# placa_1.net
KiCad netlist of a schematic drawn in EAGLE
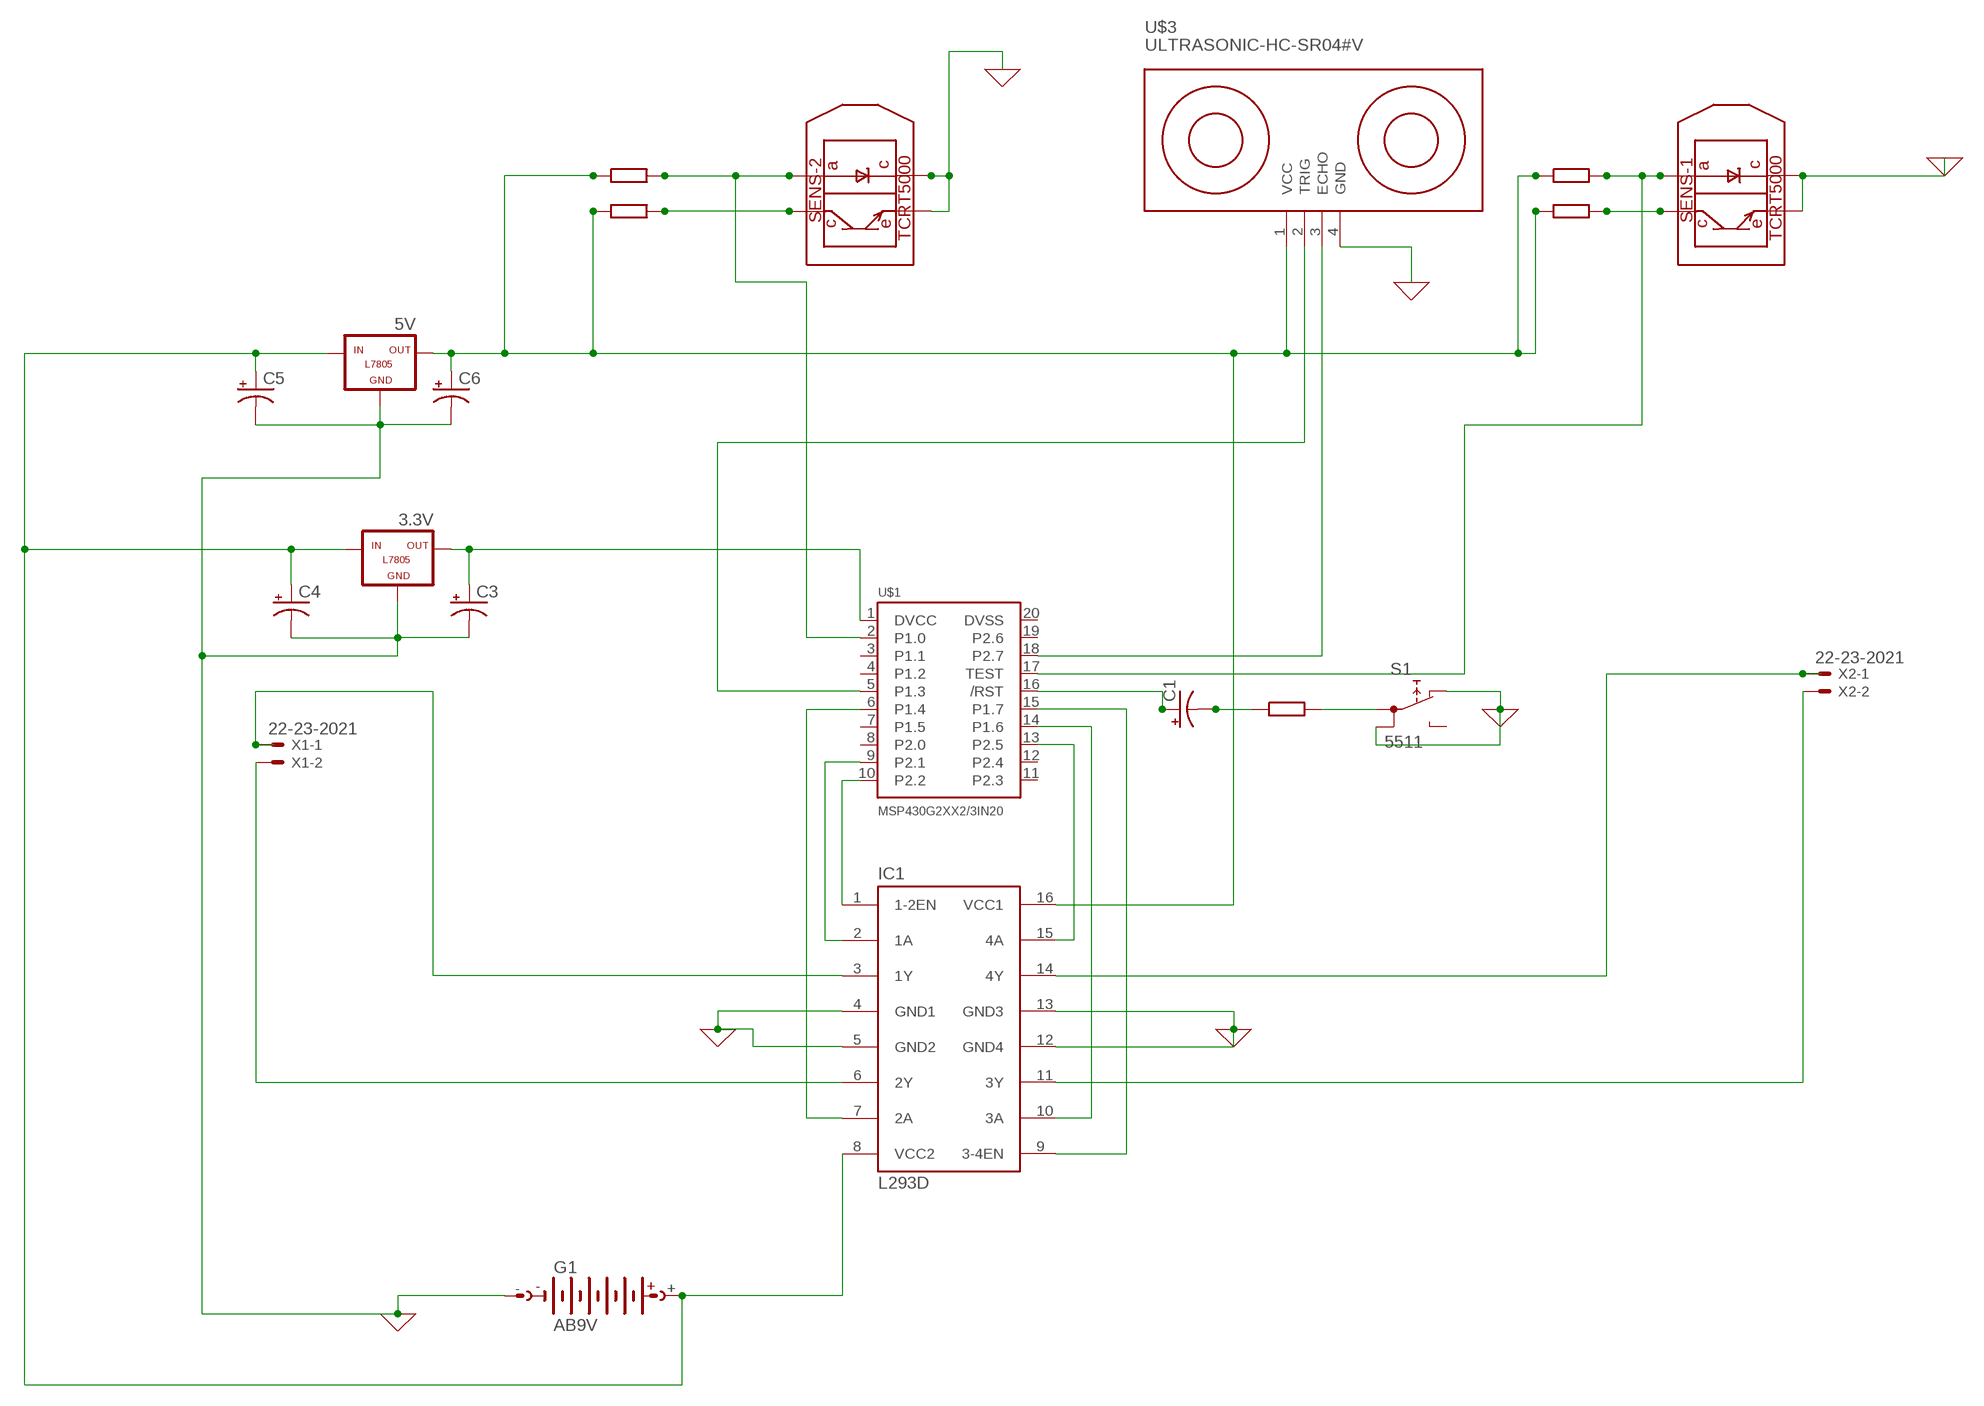
[diagram p0: schematic, sheet 1]

(export (version "E")
  (design (tool "Eeschema 10.0.6"))
  (components
    (comp (ref "3.3V")
      (value "-L7805")
      (footprint "eagle-import:L7805")
      (libsource (lib "eagle-import") (part "-L7805"))
    )
    (comp (ref "5V")
      (value "-L7805")
      (footprint "eagle-import:L7805")
      (libsource (lib "eagle-import") (part "-L7805"))
    )
    (comp (ref "C1")
      (value "CPOL-US085CS-1R")
      (footprint "eagle-import:085CS_1R")
      (libsource (lib "eagle-import") (part "CPOL-US085CS-1R"))
    )
    (comp (ref "C3")
      (value "CPOL-US085CS-1R")
      (footprint "eagle-import:085CS_1R")
      (libsource (lib "eagle-import") (part "CPOL-US085CS-1R"))
    )
    (comp (ref "C4")
      (value "CPOL-US085CS-1R")
      (footprint "eagle-import:085CS_1R")
      (libsource (lib "eagle-import") (part "CPOL-US085CS-1R"))
    )
    (comp (ref "C5")
      (value "CPOL-US085CS-1R")
      (footprint "eagle-import:085CS_1R")
      (libsource (lib "eagle-import") (part "CPOL-US085CS-1R"))
    )
    (comp (ref "C6")
      (value "CPOL-US085CS-1R")
      (footprint "eagle-import:085CS_1R")
      (libsource (lib "eagle-import") (part "CPOL-US085CS-1R"))
    )
    (comp (ref "G1")
      (value "AB9V")
      (footprint "eagle-import:AB9V")
      (libsource (lib "eagle-import") (part "AB9V"))
    )
    (comp (ref "IC1")
      (value "L293D")
      (footprint "eagle-import:DIL16")
      (libsource (lib "eagle-import") (part "L293D"))
    )
    (comp (ref "S1")
      (value "5511")
      (footprint "eagle-import:5511")
      (libsource (lib "eagle-import") (part "55?11"))
    )
    (comp (ref "SENS-1")
      (value "TCRT5000")
      (footprint "eagle-import:5000")
      (libsource (lib "eagle-import") (part "TCRT5000"))
    )
    (comp (ref "SENS-2")
      (value "TCRT5000")
      (footprint "eagle-import:5000")
      (libsource (lib "eagle-import") (part "TCRT5000"))
    )
    (comp (ref "U$1")
      (value "MSP430G2XX2/3IN20")
      (footprint "eagle-import:DIL20")
      (libsource (lib "eagle-import") (part "MSP430G2XX2/3IN20"))
    )
    (comp (ref "U$3")
      (value "ULTRASONIC-HC-SR04#V")
      (footprint "eagle-import:ULTRASONIC-HC-SR04#V")
      (libsource (lib "eagle-import") (part "ULTRASONIC-HC-SR04#V"))
    )
    (comp (ref "X1")
      (value "22-23-2021")
      (footprint "eagle-import:22-23-2021")
      (fields (field (name "MF") "MOLEX"))
      (libsource (lib "eagle-import") (part "22-23-2021"))
    )
    (comp (ref "X2")
      (value "22-23-2021")
      (footprint "eagle-import:22-23-2021")
      (fields (field (name "MF") "MOLEX"))
      (libsource (lib "eagle-import") (part "22-23-2021"))
    )
  )
  (nets
    (net (code "1") (name "/DVSS") (class "Default")
      (node (ref "U$1") (pin "20") (pinfunction "DVSS_20") (pintype "power_in"))
    )
    (net (code "2") (name "GND") (class "Default")
      (node (ref "3.3V") (pin "GND") (pinfunction "GND_GND") (pintype "input"))
      (node (ref "5V") (pin "GND") (pinfunction "GND_GND") (pintype "input"))
      (node (ref "C3") (pin "-") (pinfunction "-_-") (pintype "passive"))
      (node (ref "C4") (pin "-") (pinfunction "-_-") (pintype "passive"))
      (node (ref "C5") (pin "-") (pinfunction "-_-") (pintype "passive"))
      (node (ref "C6") (pin "-") (pinfunction "-_-") (pintype "passive"))
      (node (ref "G1") (pin "-") (pinfunction "-_-") (pintype "passive"))
      (node (ref "IC1") (pin "12") (pinfunction "GND4_12") (pintype "power_in"))
      (node (ref "IC1") (pin "13") (pinfunction "GND3_13") (pintype "power_in"))
      (node (ref "IC1") (pin "4") (pinfunction "GND1_4") (pintype "power_in"))
      (node (ref "IC1") (pin "5") (pinfunction "GND2_5") (pintype "power_in"))
      (node (ref "S1") (pin "1B") (pinfunction "1B_1B") (pintype "passive"))
      (node (ref "S1") (pin "NC") (pinfunction "NC_NC") (pintype "passive"))
      (node (ref "SENS-1") (pin "P$2") (pinfunction "P$2_P$2") (pintype "passive"))
      (node (ref "SENS-1") (pin "P$4") (pinfunction "P$4_P$4") (pintype "passive"))
      (node (ref "SENS-2") (pin "P$2") (pinfunction "P$2_P$2") (pintype "passive"))
      (node (ref "SENS-2") (pin "P$4") (pinfunction "P$4_P$4") (pintype "passive"))
      (node (ref "U$3") (pin "4") (pinfunction "GND_4") (pintype "power_in"))
    )
    (net (code "3") (name "Net-(IC1-1-2EN)") (class "Default")
      (node (ref "IC1") (pin "1") (pinfunction "1-2EN_1") (pintype "input"))
      (node (ref "U$1") (pin "10") (pinfunction "P2.2_10") (pintype "bidirectional"))
    )
    (net (code "4") (name "Net-(IC1-1A)") (class "Default")
      (node (ref "IC1") (pin "2") (pinfunction "1A_2") (pintype "input"))
      (node (ref "U$1") (pin "9") (pinfunction "P2.1_9") (pintype "bidirectional"))
    )
    (net (code "5") (name "Net-(IC1-1Y)") (class "Default")
      (node (ref "IC1") (pin "3") (pinfunction "1Y_3") (pintype "output"))
      (node (ref "X1") (pin "1") (pinfunction "S_1") (pintype "passive"))
    )
    (net (code "6") (name "Net-(IC1-2A)") (class "Default")
      (node (ref "IC1") (pin "7") (pinfunction "2A_7") (pintype "input"))
      (node (ref "U$1") (pin "6") (pinfunction "P1.4_6") (pintype "bidirectional"))
    )
    (net (code "7") (name "Net-(IC1-2Y)") (class "Default")
      (node (ref "IC1") (pin "6") (pinfunction "2Y_6") (pintype "output"))
      (node (ref "X1") (pin "2") (pinfunction "S_2") (pintype "passive"))
    )
    (net (code "8") (name "Net-(IC1-3-4EN)") (class "Default")
      (node (ref "IC1") (pin "9") (pinfunction "3-4EN_9") (pintype "input"))
      (node (ref "U$1") (pin "15") (pinfunction "P1.7_15") (pintype "bidirectional"))
    )
    (net (code "9") (name "Net-(IC1-3A)") (class "Default")
      (node (ref "IC1") (pin "10") (pinfunction "3A_10") (pintype "input"))
      (node (ref "U$1") (pin "14") (pinfunction "P1.6_14") (pintype "bidirectional"))
    )
    (net (code "10") (name "Net-(IC1-3Y)") (class "Default")
      (node (ref "IC1") (pin "11") (pinfunction "3Y_11") (pintype "output"))
      (node (ref "X2") (pin "2") (pinfunction "S_2") (pintype "passive"))
    )
    (net (code "11") (name "Net-(IC1-4A)") (class "Default")
      (node (ref "IC1") (pin "15") (pinfunction "4A_15") (pintype "input"))
      (node (ref "U$1") (pin "13") (pinfunction "P2.5_13") (pintype "bidirectional"))
    )
    (net (code "12") (name "Net-(IC1-4Y)") (class "Default")
      (node (ref "IC1") (pin "14") (pinfunction "4Y_14") (pintype "output"))
      (node (ref "X2") (pin "1") (pinfunction "S_1") (pintype "passive"))
    )
    (net (code "13") (name "Net-(IC1-VCC1)") (class "Default")
      (node (ref "5V") (pin "OUT") (pinfunction "OUT_OUT") (pintype "passive"))
      (node (ref "C6") (pin "+") (pinfunction "+_+") (pintype "passive"))
      (node (ref "IC1") (pin "16") (pinfunction "VCC1_16") (pintype "power_in"))
      (node (ref "U$3") (pin "1") (pinfunction "VCC_1") (pintype "power_in"))
    )
    (net (code "14") (name "Net-(IC1-VCC2)") (class "Default")
      (node (ref "3.3V") (pin "IN") (pinfunction "IN_IN") (pintype "input"))
      (node (ref "5V") (pin "IN") (pinfunction "IN_IN") (pintype "input"))
      (node (ref "C4") (pin "+") (pinfunction "+_+") (pintype "passive"))
      (node (ref "C5") (pin "+") (pinfunction "+_+") (pintype "passive"))
      (node (ref "G1") (pin "+") (pinfunction "+_+") (pintype "passive"))
      (node (ref "IC1") (pin "8") (pinfunction "VCC2_8") (pintype "power_in"))
    )
    (net (code "15") (name "Net-(U$1-DVCC)") (class "Default")
      (node (ref "3.3V") (pin "OUT") (pinfunction "OUT_OUT") (pintype "passive"))
      (node (ref "C3") (pin "+") (pinfunction "+_+") (pintype "passive"))
      (node (ref "U$1") (pin "1") (pinfunction "DVCC_1") (pintype "power_in"))
    )
    (net (code "16") (name "Net-(U$1-P1.0)") (class "Default")
      (node (ref "SENS-2") (pin "P$3") (pinfunction "P$3_P$3") (pintype "passive"))
      (node (ref "U$1") (pin "2") (pinfunction "P1.0_2") (pintype "bidirectional"))
    )
    (net (code "17") (name "Net-(U$1-P1.3)") (class "Default")
      (node (ref "U$1") (pin "5") (pinfunction "P1.3_5") (pintype "bidirectional"))
      (node (ref "U$3") (pin "2") (pinfunction "TRIG_2") (pintype "input"))
    )
    (net (code "18") (name "Net-(U$1-P2.7)") (class "Default")
      (node (ref "U$1") (pin "18") (pinfunction "P2.7_18") (pintype "bidirectional"))
      (node (ref "U$3") (pin "3") (pinfunction "ECHO_3") (pintype "output"))
    )
    (net (code "19") (name "Net-(U$1-TEST)") (class "Default")
      (node (ref "SENS-1") (pin "P$3") (pinfunction "P$3_P$3") (pintype "passive"))
      (node (ref "U$1") (pin "17") (pinfunction "TEST_17") (pintype "bidirectional"))
    )
    (net (code "20") (name "Net-(U$1-{slash}RST)") (class "Default")
      (node (ref "C1") (pin "+") (pinfunction "+_+") (pintype "passive"))
      (node (ref "U$1") (pin "16") (pinfunction "/RST_16") (pintype "bidirectional"))
    )
    (net (code "21") (name "unconnected-(C1-Pad-)") (class "Default")
      (node (ref "C1") (pin "-") (pinfunction "-_-") (pintype "passive"))
    )
    (net (code "22") (name "unconnected-(S1-Pad1A)") (class "Default")
      (node (ref "S1") (pin "1A") (pinfunction "1A_1A") (pintype "passive"))
    )
    (net (code "23") (name "unconnected-(S1-PadNO)") (class "Default")
      (node (ref "S1") (pin "NO") (pinfunction "NO_NO") (pintype "passive"))
    )
    (net (code "24") (name "unconnected-(SENS-1-PadP$1)") (class "Default")
      (node (ref "SENS-1") (pin "P$1") (pinfunction "P$1_P$1") (pintype "passive"))
    )
    (net (code "25") (name "unconnected-(SENS-2-PadP$1)") (class "Default")
      (node (ref "SENS-2") (pin "P$1") (pinfunction "P$1_P$1") (pintype "passive"))
    )
    (net (code "26") (name "unconnected-(U$1-P1.1-Pad3)") (class "Default")
      (node (ref "U$1") (pin "3") (pinfunction "P1.1_3") (pintype "bidirectional"))
    )
    (net (code "27") (name "unconnected-(U$1-P1.2-Pad4)") (class "Default")
      (node (ref "U$1") (pin "4") (pinfunction "P1.2_4") (pintype "bidirectional"))
    )
    (net (code "28") (name "unconnected-(U$1-P1.5-Pad7)") (class "Default")
      (node (ref "U$1") (pin "7") (pinfunction "P1.5_7") (pintype "bidirectional"))
    )
    (net (code "29") (name "unconnected-(U$1-P2.0-Pad8)") (class "Default")
      (node (ref "U$1") (pin "8") (pinfunction "P2.0_8") (pintype "bidirectional"))
    )
    (net (code "30") (name "unconnected-(U$1-P2.3-Pad11)") (class "Default")
      (node (ref "U$1") (pin "11") (pinfunction "P2.3_11") (pintype "bidirectional"))
    )
    (net (code "31") (name "unconnected-(U$1-P2.4-Pad12)") (class "Default")
      (node (ref "U$1") (pin "12") (pinfunction "P2.4_12") (pintype "bidirectional"))
    )
    (net (code "32") (name "unconnected-(U$1-P2.6-Pad19)") (class "Default")
      (node (ref "U$1") (pin "19") (pinfunction "P2.6_19") (pintype "bidirectional"))
    )
  )
)
